# Microcontroller.net
KiCad netlist of a schematic drawn in Altium Designer
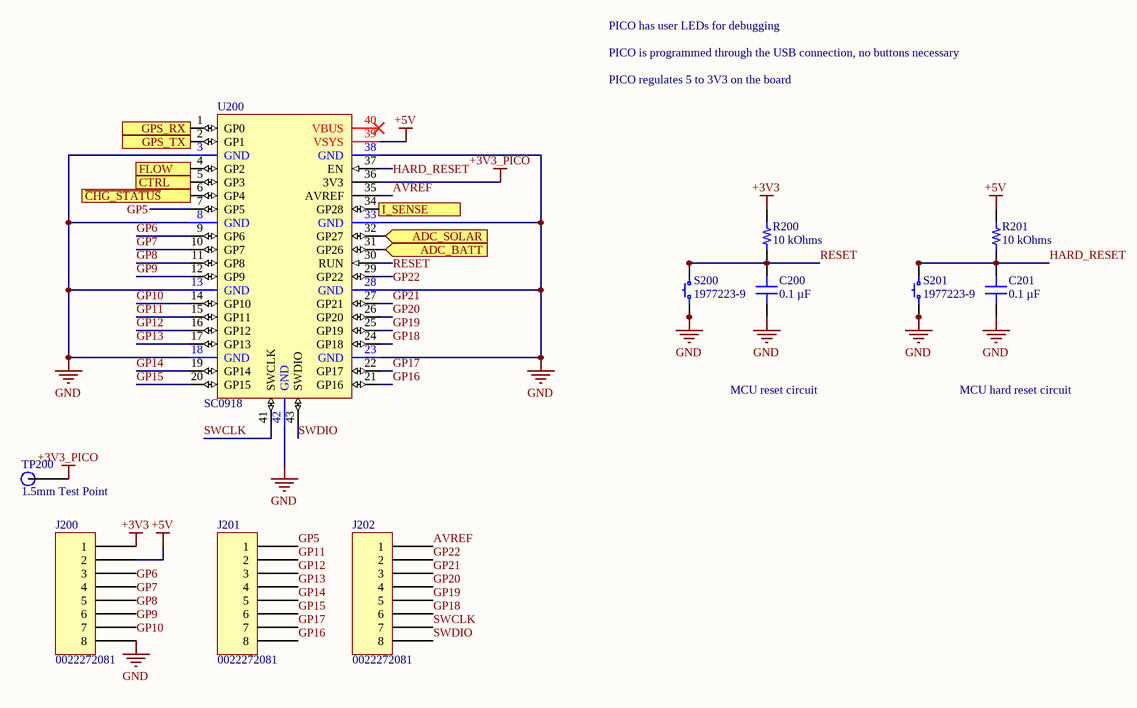
[diagram p0: Microcontroller.SchDoc]

(export (version "E")
  (design (tool "Eeschema 10.0.6"))
  (components
    (comp (ref "C200")
      (value "0.1 µF")
      (footprint "CAP 0603_1608")
      (description "CAP CER 0.1UF 25V X7R 0603")
      (fields (field (name "PART NUMBER") "C0603X104M3RAC7867") (field (name "MANUFACTURER") "KEMET"))
      (libsource (lib "Celestial Altium Library - altium_library") (part "Capacitor"))
    )
    (comp (ref "C201")
      (value "0.1 µF")
      (footprint "CAP 0603_1608")
      (description "CAP CER 0.1UF 25V X7R 0603")
      (fields (field (name "PART NUMBER") "C0603X104M3RAC7867") (field (name "MANUFACTURER") "KEMET"))
      (libsource (lib "Celestial Altium Library - altium_library") (part "Capacitor"))
    )
    (comp (ref "J200")
      (value "0022272081")
      (footprint "MOLEX KK 0022272081")
      (description "CONN HEADER VERT 8POS 2.54MM")
      (fields (field (name "MANUFACTURER") "Molex"))
      (libsource (lib "Celestial Altium Library - altium_library") (part "8 Pin"))
    )
    (comp (ref "J201")
      (value "0022272081")
      (footprint "MOLEX KK 0022272081")
      (description "CONN HEADER VERT 8POS 2.54MM")
      (fields (field (name "MANUFACTURER") "Molex"))
      (libsource (lib "Celestial Altium Library - altium_library") (part "8 Pin"))
    )
    (comp (ref "J202")
      (value "0022272081")
      (footprint "MOLEX KK 0022272081")
      (description "CONN HEADER VERT 8POS 2.54MM")
      (fields (field (name "MANUFACTURER") "Molex"))
      (libsource (lib "Celestial Altium Library - altium_library") (part "8 Pin"))
    )
    (comp (ref "R200")
      (value "10 kOhms")
      (footprint "RES 0603_1608")
      (description "RES SMD 10K OHM 1% 1/10W 0603")
      (fields (field (name "PART NUMBER") "RT0603FRE0710KL") (field (name "MANUFACTURER") "Yageo"))
      (libsource (lib "Celestial Altium Library - altium_library") (part "Resistor"))
    )
    (comp (ref "R201")
      (value "10 kOhms")
      (footprint "RES 0603_1608")
      (description "RES SMD 10K OHM 1% 1/10W 0603")
      (fields (field (name "PART NUMBER") "RT0603FRE0710KL") (field (name "MANUFACTURER") "Yageo"))
      (libsource (lib "Celestial Altium Library - altium_library") (part "Resistor"))
    )
    (comp (ref "S200")
      (value "1977223-9")
      (footprint "TE FSM4JSMA")
      (description "SWITCH TACTILE SPST-NO 0.05A 24V")
      (fields (field (name "MANUFACTURER") "TE Connectivity ALCOSWITCH Switches"))
      (libsource (lib "Celestial Altium Library - altium_library") (part "SPST-NO 4 PIN"))
    )
    (comp (ref "S201")
      (value "1977223-9")
      (footprint "TE FSM4JSMA")
      (description "SWITCH TACTILE SPST-NO 0.05A 24V")
      (fields (field (name "MANUFACTURER") "TE Connectivity ALCOSWITCH Switches"))
      (libsource (lib "Celestial Altium Library - altium_library") (part "SPST-NO 4 PIN"))
    )
    (comp (ref "TP200")
      (value "1.5mm Test Point")
      (footprint "1mm Test Point-Footprint-1")
      (description "1.5mm Test Point 0.75mm hole size")
      (libsource (lib "Americas- Environmental Engineering Club- University of Victoria") (part "1mm Test Point-Symbol-1"))
    )
    (comp (ref "U200")
      (value "SC0918")
      (footprint "New footprint 1")
      (description "Raspberry Pi Pico W")
      (libsource (lib "Americas- Environmental Engineering Club- University of Victoria") (part "Raspberry Pi Pico"))
    )
  )
  (nets
    (net (code "1") (name "+3V3") (class "Default")
      (node (ref "J200") (pin "1") (pinfunction "1_1") (pintype "passive"))
      (node (ref "R200") (pin "2") (pinfunction "2_2") (pintype "passive"))
    )
    (net (code "2") (name "+3V3_PICO") (class "Default")
      (node (ref "TP200") (pin "1") (pinfunction "1_1") (pintype "passive"))
      (node (ref "U200") (pin "36") (pinfunction "3V3_36") (pintype "power_in"))
    )
    (net (code "3") (name "+5V") (class "Default")
      (node (ref "J200") (pin "2") (pinfunction "2_2") (pintype "passive"))
      (node (ref "R201") (pin "2") (pinfunction "2_2") (pintype "passive"))
      (node (ref "U200") (pin "39") (pinfunction "VSYS_39") (pintype "power_in"))
    )
    (net (code "4") (name "/ADC_BATT") (class "Default")
      (node (ref "U200") (pin "31") (pinfunction "GP26_31") (pintype "bidirectional"))
    )
    (net (code "5") (name "/ADC_SOLAR") (class "Default")
      (node (ref "U200") (pin "32") (pinfunction "GP27_32") (pintype "bidirectional"))
    )
    (net (code "6") (name "/AVREF") (class "Default")
      (node (ref "J202") (pin "1") (pinfunction "1_1") (pintype "passive"))
      (node (ref "U200") (pin "35") (pinfunction "AVREF_35") (pintype "power_in"))
    )
    (net (code "7") (name "/CTRL") (class "Default")
      (node (ref "U200") (pin "5") (pinfunction "GP3_5") (pintype "bidirectional"))
    )
    (net (code "8") (name "/FLOW") (class "Default")
      (node (ref "U200") (pin "4") (pinfunction "GP2_4") (pintype "bidirectional"))
    )
    (net (code "9") (name "/GP5") (class "Default")
      (node (ref "J201") (pin "1") (pinfunction "1_1") (pintype "passive"))
      (node (ref "U200") (pin "7") (pinfunction "GP5_7") (pintype "bidirectional"))
    )
    (net (code "10") (name "/GP6") (class "Default")
      (node (ref "J200") (pin "3") (pinfunction "3_3") (pintype "passive"))
      (node (ref "U200") (pin "9") (pinfunction "GP6_9") (pintype "bidirectional"))
    )
    (net (code "11") (name "/GP7") (class "Default")
      (node (ref "J200") (pin "4") (pinfunction "4_4") (pintype "passive"))
      (node (ref "U200") (pin "10") (pinfunction "GP7_10") (pintype "bidirectional"))
    )
    (net (code "12") (name "/GP8") (class "Default")
      (node (ref "J200") (pin "5") (pinfunction "5_5") (pintype "passive"))
      (node (ref "U200") (pin "11") (pinfunction "GP8_11") (pintype "bidirectional"))
    )
    (net (code "13") (name "/GP9") (class "Default")
      (node (ref "J200") (pin "6") (pinfunction "6_6") (pintype "passive"))
      (node (ref "U200") (pin "12") (pinfunction "GP9_12") (pintype "bidirectional"))
    )
    (net (code "14") (name "/GP10") (class "Default")
      (node (ref "J200") (pin "7") (pinfunction "7_7") (pintype "passive"))
      (node (ref "U200") (pin "14") (pinfunction "GP10_14") (pintype "bidirectional"))
    )
    (net (code "15") (name "/GP11") (class "Default")
      (node (ref "J201") (pin "2") (pinfunction "2_2") (pintype "passive"))
      (node (ref "U200") (pin "15") (pinfunction "GP11_15") (pintype "bidirectional"))
    )
    (net (code "16") (name "/GP12") (class "Default")
      (node (ref "J201") (pin "3") (pinfunction "3_3") (pintype "passive"))
      (node (ref "U200") (pin "16") (pinfunction "GP12_16") (pintype "bidirectional"))
    )
    (net (code "17") (name "/GP13") (class "Default")
      (node (ref "J201") (pin "4") (pinfunction "4_4") (pintype "passive"))
      (node (ref "U200") (pin "17") (pinfunction "GP13_17") (pintype "bidirectional"))
    )
    (net (code "18") (name "/GP14") (class "Default")
      (node (ref "J201") (pin "5") (pinfunction "5_5") (pintype "passive"))
      (node (ref "U200") (pin "19") (pinfunction "GP14_19") (pintype "bidirectional"))
    )
    (net (code "19") (name "/GP15") (class "Default")
      (node (ref "J201") (pin "6") (pinfunction "6_6") (pintype "passive"))
      (node (ref "U200") (pin "20") (pinfunction "GP15_20") (pintype "bidirectional"))
    )
    (net (code "20") (name "/GP16") (class "Default")
      (node (ref "J201") (pin "8") (pinfunction "8_8") (pintype "passive"))
      (node (ref "U200") (pin "21") (pinfunction "GP16_21") (pintype "bidirectional"))
    )
    (net (code "21") (name "/GP17") (class "Default")
      (node (ref "J201") (pin "7") (pinfunction "7_7") (pintype "passive"))
      (node (ref "U200") (pin "22") (pinfunction "GP17_22") (pintype "bidirectional"))
    )
    (net (code "22") (name "/GP18") (class "Default")
      (node (ref "J202") (pin "6") (pinfunction "6_6") (pintype "passive"))
      (node (ref "U200") (pin "24") (pinfunction "GP18_24") (pintype "bidirectional"))
    )
    (net (code "23") (name "/GP19") (class "Default")
      (node (ref "J202") (pin "5") (pinfunction "5_5") (pintype "passive"))
      (node (ref "U200") (pin "25") (pinfunction "GP19_25") (pintype "bidirectional"))
    )
    (net (code "24") (name "/GP20") (class "Default")
      (node (ref "J202") (pin "4") (pinfunction "4_4") (pintype "passive"))
      (node (ref "U200") (pin "26") (pinfunction "GP20_26") (pintype "bidirectional"))
    )
    (net (code "25") (name "/GP21") (class "Default")
      (node (ref "J202") (pin "3") (pinfunction "3_3") (pintype "passive"))
      (node (ref "U200") (pin "27") (pinfunction "GP21_27") (pintype "bidirectional"))
    )
    (net (code "26") (name "/GP22") (class "Default")
      (node (ref "J202") (pin "2") (pinfunction "2_2") (pintype "passive"))
      (node (ref "U200") (pin "29") (pinfunction "GP22_29") (pintype "bidirectional"))
    )
    (net (code "27") (name "/GPS_RX") (class "Default")
      (node (ref "U200") (pin "1") (pinfunction "GP0_1") (pintype "bidirectional"))
    )
    (net (code "28") (name "/GPS_TX") (class "Default")
      (node (ref "U200") (pin "2") (pinfunction "GP1_2") (pintype "bidirectional"))
    )
    (net (code "29") (name "/HARD_RESET") (class "Default")
      (node (ref "C201") (pin "2") (pinfunction "2_2") (pintype "passive"))
      (node (ref "R201") (pin "1") (pinfunction "1_1") (pintype "passive"))
      (node (ref "S201") (pin "3") (pinfunction "3_3") (pintype "passive"))
      (node (ref "S201") (pin "4") (pinfunction "4_4") (pintype "passive"))
      (node (ref "U200") (pin "37") (pinfunction "EN_37") (pintype "input"))
    )
    (net (code "30") (name "/I_SENSE") (class "Default")
      (node (ref "U200") (pin "34") (pinfunction "GP28_34") (pintype "bidirectional"))
    )
    (net (code "31") (name "/RESET") (class "Default")
      (node (ref "C200") (pin "2") (pinfunction "2_2") (pintype "passive"))
      (node (ref "R200") (pin "1") (pinfunction "1_1") (pintype "passive"))
      (node (ref "S200") (pin "3") (pinfunction "3_3") (pintype "passive"))
      (node (ref "S200") (pin "4") (pinfunction "4_4") (pintype "passive"))
      (node (ref "U200") (pin "30") (pinfunction "RUN_30") (pintype "input"))
    )
    (net (code "32") (name "/SWCLK") (class "Default")
      (node (ref "J202") (pin "7") (pinfunction "7_7") (pintype "passive"))
      (node (ref "U200") (pin "41") (pinfunction "SWCLK_41") (pintype "bidirectional"))
    )
    (net (code "33") (name "/SWDIO") (class "Default")
      (node (ref "J202") (pin "8") (pinfunction "8_8") (pintype "passive"))
      (node (ref "U200") (pin "43") (pinfunction "SWDIO_43") (pintype "bidirectional"))
    )
    (net (code "34") (name "/~{CHG_STATUS}") (class "Default")
      (node (ref "U200") (pin "6") (pinfunction "GP4_6") (pintype "bidirectional"))
    )
    (net (code "35") (name "GND") (class "Default")
      (node (ref "C200") (pin "1") (pinfunction "1_1") (pintype "passive"))
      (node (ref "C201") (pin "1") (pinfunction "1_1") (pintype "passive"))
      (node (ref "J200") (pin "8") (pinfunction "8_8") (pintype "passive"))
      (node (ref "S200") (pin "1") (pinfunction "1_1") (pintype "passive"))
      (node (ref "S200") (pin "2") (pinfunction "2_2") (pintype "passive"))
      (node (ref "S201") (pin "1") (pinfunction "1_1") (pintype "passive"))
      (node (ref "S201") (pin "2") (pinfunction "2_2") (pintype "passive"))
      (node (ref "U200") (pin "13") (pinfunction "GND_13") (pintype "power_in"))
      (node (ref "U200") (pin "18") (pinfunction "GND_18") (pintype "power_in"))
      (node (ref "U200") (pin "23") (pinfunction "GND_23") (pintype "power_in"))
      (node (ref "U200") (pin "28") (pinfunction "GND_28") (pintype "power_in"))
      (node (ref "U200") (pin "3") (pinfunction "GND_3") (pintype "power_in"))
      (node (ref "U200") (pin "33") (pinfunction "GND_33") (pintype "power_in"))
      (node (ref "U200") (pin "38") (pinfunction "GND_38") (pintype "power_in"))
      (node (ref "U200") (pin "42") (pinfunction "GND_42") (pintype "power_in"))
      (node (ref "U200") (pin "8") (pinfunction "GND_8") (pintype "power_in"))
    )
    (net (code "36") (name "unconnected-(U200-VBUS-Pad40)") (class "Default")
      (node (ref "U200") (pin "40") (pinfunction "VBUS_40") (pintype "power_in+no_connect"))
    )
  )
)
